# Practica1_v2.net
KiCad netlist of a schematic drawn in EAGLE
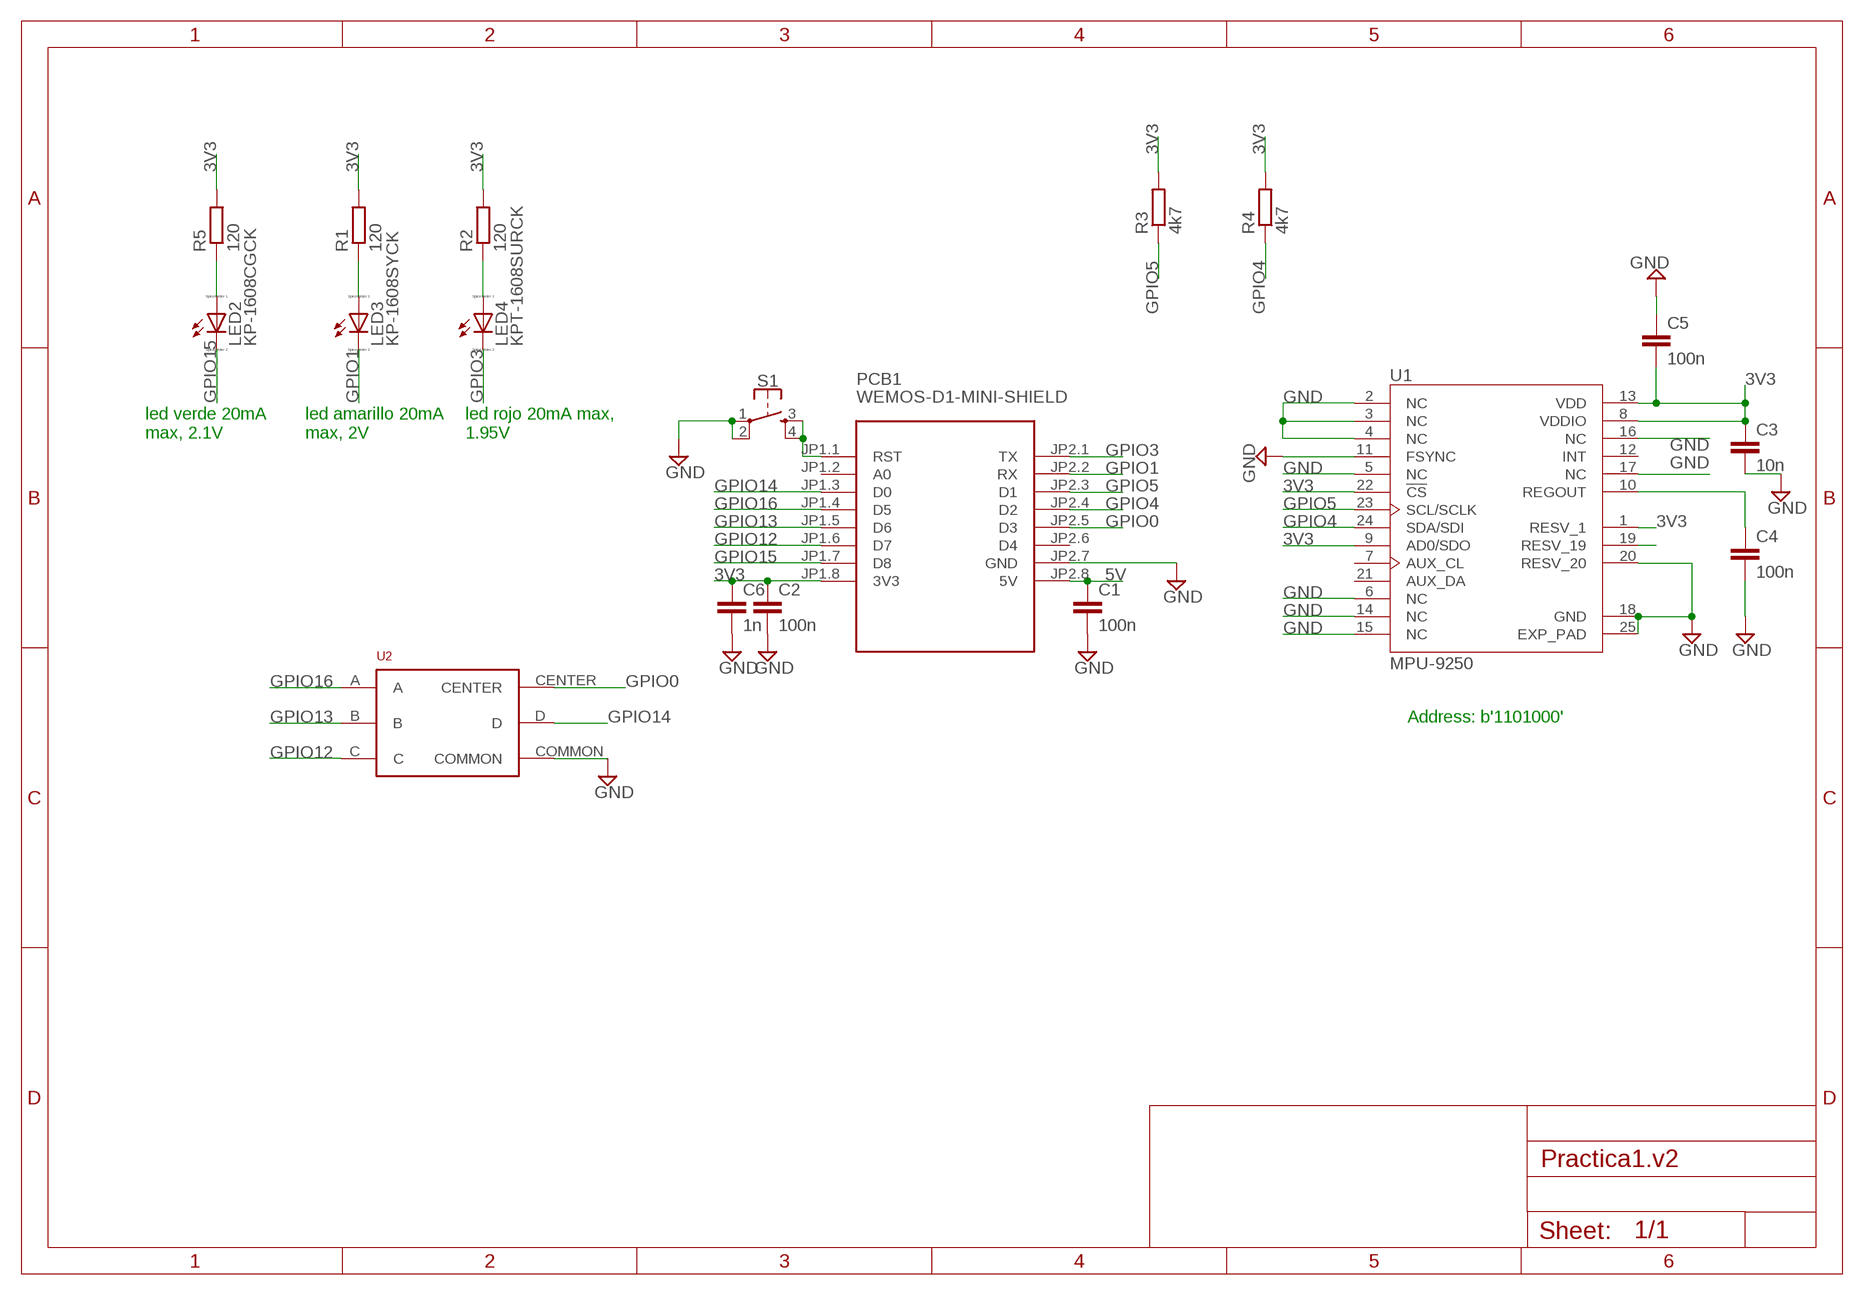
[diagram p0: schematic, sheet 1]

(export (version "E")
  (design (tool "Eeschema 10.0.6"))
  (components
    (comp (ref "C1")
      (value "100n")
      (footprint "eagle-import:C0805")
      (libsource (lib "eagle-import") (part "C-EUC0805"))
    )
    (comp (ref "C2")
      (value "100n")
      (footprint "eagle-import:C0805")
      (libsource (lib "eagle-import") (part "C-EUC0805"))
    )
    (comp (ref "C3")
      (value "10n")
      (footprint "eagle-import:C0603")
      (libsource (lib "eagle-import") (part "C-EUC0603"))
    )
    (comp (ref "C4")
      (value "100n")
      (footprint "eagle-import:C0805")
      (libsource (lib "eagle-import") (part "C-EUC0805"))
    )
    (comp (ref "C5")
      (value "100n")
      (footprint "eagle-import:C0805")
      (libsource (lib "eagle-import") (part "C-EUC0805"))
    )
    (comp (ref "C6")
      (value "1n")
      (footprint "eagle-import:C0402")
      (libsource (lib "eagle-import") (part "C-EUC0402"))
    )
    (comp (ref "LED2")
      (value "KP-1608CGCK")
      (footprint "eagle-import:LED_SML0603")
      (libsource (lib "eagle-import") (part "LED_ESML0603"))
    )
    (comp (ref "LED3")
      (value "KP-1608SYCK")
      (footprint "eagle-import:LED_SML0603")
      (libsource (lib "eagle-import") (part "LED_ESML0603"))
    )
    (comp (ref "LED4")
      (value "KPT-1608SURCK")
      (footprint "eagle-import:LED_SML0603")
      (libsource (lib "eagle-import") (part "LED_ESML0603"))
    )
    (comp (ref "PCB1")
      (value "WEMOS-D1-MINI-SHIELD")
      (footprint "eagle-import:WEMOS-D1-MINI-SHIELD")
      (libsource (lib "eagle-import") (part "WEMOS-D1-MINI-SHIELD"))
    )
    (comp (ref "R1")
      (value "120")
      (footprint "eagle-import:R1206")
      (libsource (lib "eagle-import") (part "R-EU_R1206"))
    )
    (comp (ref "R2")
      (value "120")
      (footprint "eagle-import:R1206")
      (libsource (lib "eagle-import") (part "R-EU_R1206"))
    )
    (comp (ref "R3")
      (value "4k7")
      (footprint "eagle-import:R1206")
      (libsource (lib "eagle-import") (part "R-EU_R1206"))
    )
    (comp (ref "R4")
      (value "4k7")
      (footprint "eagle-import:R1206")
      (libsource (lib "eagle-import") (part "R-EU_R1206"))
    )
    (comp (ref "R5")
      (value "120")
      (footprint "eagle-import:R1206")
      (libsource (lib "eagle-import") (part "R-EU_R1206"))
    )
    (comp (ref "S1")
      (value "MOMENTARY-SWITCH-SPST-2-SMD-5.2MM-TALL")
      (footprint "eagle-import:TACTILE_SWITCH_SMD_5.2MM")
      (libsource (lib "eagle-import") (part "MOMENTARY-SWITCH-SPST-2-SMD-5.2MM-TALL"))
    )
    (comp (ref "U1")
      (value "MPU-9250")
      (footprint "eagle-import:QFN40P300X300X105-25N")
      (fields (field (name "MANUFACTURER") "TDK InvenSense"))
      (libsource (lib "eagle-import") (part "MPU-9250"))
    )
    (comp (ref "U2")
      (value "JOYSTICK")
      (footprint "eagle-import:JOYSTICK_516_316")
      (fields (field (name "MANUFACTURER") "Alps") (field (name "PARTNUMBER") "SKQUCAA010"))
      (libsource (lib "eagle-import") (part "JOYSTICK"))
    )
  )
  (nets
    (net (code "1") (name "/3V3") (class "Default")
      (node (ref "C2") (pin "1") (pinfunction "1_1") (pintype "passive"))
      (node (ref "C3") (pin "1") (pinfunction "1_1") (pintype "passive"))
      (node (ref "C5") (pin "2") (pinfunction "2_2") (pintype "passive"))
      (node (ref "C6") (pin "1") (pinfunction "1_1") (pintype "passive"))
      (node (ref "PCB1") (pin "JP1.8") (pinfunction "3V3_JP1.8") (pintype "power_in"))
      (node (ref "R1") (pin "2") (pinfunction "2_2") (pintype "passive"))
      (node (ref "R2") (pin "2") (pinfunction "2_2") (pintype "passive"))
      (node (ref "R3") (pin "2") (pinfunction "2_2") (pintype "passive"))
      (node (ref "R4") (pin "2") (pinfunction "2_2") (pintype "passive"))
      (node (ref "R5") (pin "2") (pinfunction "2_2") (pintype "passive"))
      (node (ref "U1") (pin "1") (pinfunction "RESV_1_1") (pintype "passive"))
      (node (ref "U1") (pin "13") (pinfunction "VDD_13") (pintype "power_in"))
      (node (ref "U1") (pin "22") (pinfunction "~{CS}_22") (pintype "input"))
      (node (ref "U1") (pin "8") (pinfunction "VDDIO_8") (pintype "power_in"))
      (node (ref "U1") (pin "9") (pinfunction "AD0/SDO_9") (pintype "output"))
    )
    (net (code "2") (name "/5V") (class "Default")
      (node (ref "C1") (pin "1") (pinfunction "1_1") (pintype "passive"))
      (node (ref "PCB1") (pin "JP2.8") (pinfunction "5V_JP2.8") (pintype "power_in"))
    )
    (net (code "3") (name "/GPIO0") (class "Default")
      (node (ref "PCB1") (pin "JP2.5") (pinfunction "D3_JP2.5") (pintype "bidirectional"))
      (node (ref "U2") (pin "CENTER") (pinfunction "CENTER_CENTER") (pintype "bidirectional"))
    )
    (net (code "4") (name "/GPIO1") (class "Default")
      (node (ref "LED3") (pin "C") (pinfunction "C_C") (pintype "passive"))
      (node (ref "PCB1") (pin "JP2.2") (pinfunction "RX_JP2.2") (pintype "bidirectional"))
    )
    (net (code "5") (name "/GPIO3") (class "Default")
      (node (ref "LED4") (pin "C") (pinfunction "C_C") (pintype "passive"))
      (node (ref "PCB1") (pin "JP2.1") (pinfunction "TX_JP2.1") (pintype "bidirectional"))
    )
    (net (code "6") (name "/GPIO4") (class "Default")
      (node (ref "PCB1") (pin "JP2.4") (pinfunction "D2_JP2.4") (pintype "bidirectional"))
      (node (ref "R4") (pin "1") (pinfunction "1_1") (pintype "passive"))
      (node (ref "U1") (pin "24") (pinfunction "SDA/SDI_24") (pintype "bidirectional"))
    )
    (net (code "7") (name "/GPIO5") (class "Default")
      (node (ref "PCB1") (pin "JP2.3") (pinfunction "D1_JP2.3") (pintype "bidirectional"))
      (node (ref "R3") (pin "1") (pinfunction "1_1") (pintype "passive"))
      (node (ref "U1") (pin "23") (pinfunction "SCL/SCLK_23") (pintype "input"))
    )
    (net (code "8") (name "/GPIO12") (class "Default")
      (node (ref "PCB1") (pin "JP1.6") (pinfunction "D7_JP1.6") (pintype "bidirectional"))
      (node (ref "U2") (pin "C") (pinfunction "C_C") (pintype "bidirectional"))
    )
    (net (code "9") (name "/GPIO13") (class "Default")
      (node (ref "PCB1") (pin "JP1.5") (pinfunction "D6_JP1.5") (pintype "bidirectional"))
      (node (ref "U2") (pin "B") (pinfunction "B_B") (pintype "bidirectional"))
    )
    (net (code "10") (name "/GPIO14") (class "Default")
      (node (ref "PCB1") (pin "JP1.3") (pinfunction "D0_JP1.3") (pintype "bidirectional"))
      (node (ref "U2") (pin "D") (pinfunction "D_D") (pintype "bidirectional"))
    )
    (net (code "11") (name "/GPIO15") (class "Default")
      (node (ref "LED2") (pin "C") (pinfunction "C_C") (pintype "passive"))
      (node (ref "PCB1") (pin "JP1.7") (pinfunction "D8_JP1.7") (pintype "bidirectional"))
    )
    (net (code "12") (name "/GPIO16") (class "Default")
      (node (ref "PCB1") (pin "JP1.4") (pinfunction "D5_JP1.4") (pintype "bidirectional"))
      (node (ref "U2") (pin "A") (pinfunction "A_A") (pintype "bidirectional"))
    )
    (net (code "13") (name "GND") (class "Default")
      (node (ref "C1") (pin "2") (pinfunction "2_2") (pintype "passive"))
      (node (ref "C2") (pin "2") (pinfunction "2_2") (pintype "passive"))
      (node (ref "C3") (pin "2") (pinfunction "2_2") (pintype "passive"))
      (node (ref "C4") (pin "2") (pinfunction "2_2") (pintype "passive"))
      (node (ref "C5") (pin "1") (pinfunction "1_1") (pintype "passive"))
      (node (ref "C6") (pin "2") (pinfunction "2_2") (pintype "passive"))
      (node (ref "PCB1") (pin "JP2.7") (pinfunction "GND_JP2.7") (pintype "power_in"))
      (node (ref "S1") (pin "1") (pinfunction "1_1") (pintype "passive"))
      (node (ref "S1") (pin "2") (pinfunction "2_2") (pintype "passive"))
      (node (ref "U1") (pin "11") (pinfunction "FSYNC_11") (pintype "output"))
      (node (ref "U1") (pin "14") (pinfunction "NC_14") (pintype "bidirectional"))
      (node (ref "U1") (pin "15") (pinfunction "NC_15") (pintype "bidirectional"))
      (node (ref "U1") (pin "16") (pinfunction "NC_16") (pintype "bidirectional"))
      (node (ref "U1") (pin "17") (pinfunction "NC_17") (pintype "bidirectional"))
      (node (ref "U1") (pin "18") (pinfunction "GND_18") (pintype "power_in"))
      (node (ref "U1") (pin "2") (pinfunction "NC_2") (pintype "bidirectional"))
      (node (ref "U1") (pin "20") (pinfunction "RESV_20_20") (pintype "passive"))
      (node (ref "U1") (pin "25") (pinfunction "EXP_PAD_25") (pintype "power_in"))
      (node (ref "U1") (pin "3") (pinfunction "NC_3") (pintype "bidirectional"))
      (node (ref "U1") (pin "4") (pinfunction "NC_4") (pintype "bidirectional"))
      (node (ref "U1") (pin "5") (pinfunction "NC_5") (pintype "input"))
      (node (ref "U1") (pin "6") (pinfunction "NC_6") (pintype "bidirectional"))
      (node (ref "U2") (pin "COMMON") (pinfunction "COMMON_COMMON") (pintype "bidirectional"))
    )
    (net (code "14") (name "Net-(LED2-PadA)") (class "Default")
      (node (ref "LED2") (pin "A") (pinfunction "A_A") (pintype "passive"))
      (node (ref "R5") (pin "1") (pinfunction "1_1") (pintype "passive"))
    )
    (net (code "15") (name "Net-(LED3-PadA)") (class "Default")
      (node (ref "LED3") (pin "A") (pinfunction "A_A") (pintype "passive"))
      (node (ref "R1") (pin "1") (pinfunction "1_1") (pintype "passive"))
    )
    (net (code "16") (name "Net-(LED4-PadA)") (class "Default")
      (node (ref "LED4") (pin "A") (pinfunction "A_A") (pintype "passive"))
      (node (ref "R2") (pin "1") (pinfunction "1_1") (pintype "passive"))
    )
    (net (code "17") (name "Net-(PCB1-RST)") (class "Default")
      (node (ref "PCB1") (pin "JP1.1") (pinfunction "RST_JP1.1") (pintype "bidirectional"))
      (node (ref "S1") (pin "3") (pinfunction "3_3") (pintype "passive"))
      (node (ref "S1") (pin "4") (pinfunction "4_4") (pintype "passive"))
    )
    (net (code "18") (name "Net-(U1-REGOUT)") (class "Default")
      (node (ref "C4") (pin "1") (pinfunction "1_1") (pintype "passive"))
      (node (ref "U1") (pin "10") (pinfunction "REGOUT_10") (pintype "output"))
    )
    (net (code "19") (name "unconnected-(PCB1-A0-PadJP1.2)") (class "Default")
      (node (ref "PCB1") (pin "JP1.2") (pinfunction "A0_JP1.2") (pintype "bidirectional"))
    )
    (net (code "20") (name "unconnected-(PCB1-D4-PadJP2.6)") (class "Default")
      (node (ref "PCB1") (pin "JP2.6") (pinfunction "D4_JP2.6") (pintype "bidirectional"))
    )
    (net (code "21") (name "unconnected-(U1-AUX_CL-Pad7)") (class "Default")
      (node (ref "U1") (pin "7") (pinfunction "AUX_CL_7") (pintype "input"))
    )
    (net (code "22") (name "unconnected-(U1-AUX_DA-Pad21)") (class "Default")
      (node (ref "U1") (pin "21") (pinfunction "AUX_DA_21") (pintype "input"))
    )
    (net (code "23") (name "unconnected-(U1-INT-Pad12)") (class "Default")
      (node (ref "U1") (pin "12") (pinfunction "INT_12") (pintype "output"))
    )
    (net (code "24") (name "unconnected-(U1-RESV_19-Pad19)") (class "Default")
      (node (ref "U1") (pin "19") (pinfunction "RESV_19_19") (pintype "passive"))
    )
  )
)
